# SerialSnifferDIN.net
KiCad netlist of a schematic drawn in EAGLE
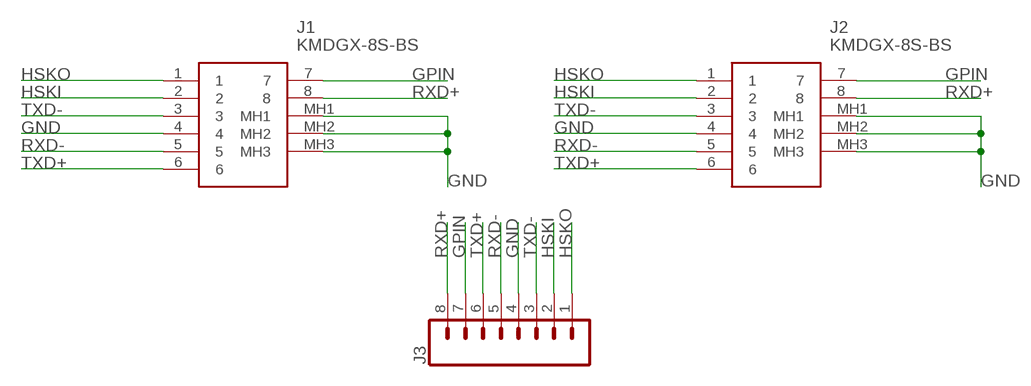
[diagram p0: schematic, sheet 1]

(export (version "E")
  (design (tool "Eeschema 10.0.6"))
  (components
    (comp (ref "J1")
      (value "KMDGX-8S-BS")
      (footprint "eagle-import:KMDGX8SBS")
      (fields (field (name "MOUSER_PART_NUMBER") "806-KMDGX-8S-BS"))
      (libsource (lib "eagle-import") (part "KMDGX-8S-BS"))
    )
    (comp (ref "J2")
      (value "KMDGX-8S-BS")
      (footprint "eagle-import:KMDGX8SBS")
      (fields (field (name "MOUSER_PART_NUMBER") "806-KMDGX-8S-BS"))
      (libsource (lib "eagle-import") (part "KMDGX-8S-BS"))
    )
    (comp (ref "J3")
      (value "CONN_08LOCK_LONGPADS")
      (footprint "eagle-import:1X08_LOCK_LONGPADS")
      (libsource (lib "eagle-import") (part "CONN_08LOCK_LONGPADS"))
    )
  )
  (nets
    (net (code "1") (name "/GND") (class "Default")
      (node (ref "J1") (pin "4") (pinfunction "4_4") (pintype "bidirectional"))
      (node (ref "J1") (pin "MH1") (pinfunction "MH1_MH1") (pintype "bidirectional"))
      (node (ref "J1") (pin "MH2") (pinfunction "MH2_MH2") (pintype "bidirectional"))
      (node (ref "J1") (pin "MH3") (pinfunction "MH3_MH3") (pintype "bidirectional"))
      (node (ref "J2") (pin "4") (pinfunction "4_4") (pintype "bidirectional"))
      (node (ref "J2") (pin "MH1") (pinfunction "MH1_MH1") (pintype "bidirectional"))
      (node (ref "J2") (pin "MH2") (pinfunction "MH2_MH2") (pintype "bidirectional"))
      (node (ref "J2") (pin "MH3") (pinfunction "MH3_MH3") (pintype "bidirectional"))
      (node (ref "J3") (pin "4") (pinfunction "4_4") (pintype "passive"))
    )
    (net (code "2") (name "/GPIN") (class "Default")
      (node (ref "J1") (pin "7") (pinfunction "7_7") (pintype "bidirectional"))
      (node (ref "J2") (pin "7") (pinfunction "7_7") (pintype "bidirectional"))
      (node (ref "J3") (pin "7") (pinfunction "7_7") (pintype "passive"))
    )
    (net (code "3") (name "/HSKI") (class "Default")
      (node (ref "J1") (pin "2") (pinfunction "2_2") (pintype "bidirectional"))
      (node (ref "J2") (pin "2") (pinfunction "2_2") (pintype "bidirectional"))
      (node (ref "J3") (pin "2") (pinfunction "2_2") (pintype "passive"))
    )
    (net (code "4") (name "/HSKO") (class "Default")
      (node (ref "J1") (pin "1") (pinfunction "1_1") (pintype "bidirectional"))
      (node (ref "J2") (pin "1") (pinfunction "1_1") (pintype "bidirectional"))
      (node (ref "J3") (pin "1") (pinfunction "1_1") (pintype "passive"))
    )
    (net (code "5") (name "/RXD+") (class "Default")
      (node (ref "J1") (pin "8") (pinfunction "8_8") (pintype "bidirectional"))
      (node (ref "J2") (pin "8") (pinfunction "8_8") (pintype "bidirectional"))
      (node (ref "J3") (pin "8") (pinfunction "8_8") (pintype "passive"))
    )
    (net (code "6") (name "/RXD-") (class "Default")
      (node (ref "J1") (pin "5") (pinfunction "5_5") (pintype "bidirectional"))
      (node (ref "J2") (pin "5") (pinfunction "5_5") (pintype "bidirectional"))
      (node (ref "J3") (pin "5") (pinfunction "5_5") (pintype "passive"))
    )
    (net (code "7") (name "/TXD+") (class "Default")
      (node (ref "J1") (pin "6") (pinfunction "6_6") (pintype "bidirectional"))
      (node (ref "J2") (pin "6") (pinfunction "6_6") (pintype "bidirectional"))
      (node (ref "J3") (pin "6") (pinfunction "6_6") (pintype "passive"))
    )
    (net (code "8") (name "/TXD-") (class "Default")
      (node (ref "J1") (pin "3") (pinfunction "3_3") (pintype "bidirectional"))
      (node (ref "J2") (pin "3") (pinfunction "3_3") (pintype "bidirectional"))
      (node (ref "J3") (pin "3") (pinfunction "3_3") (pintype "passive"))
    )
  )
)
